# Programmer.net
KiCad netlist of a schematic drawn in Altium Designer
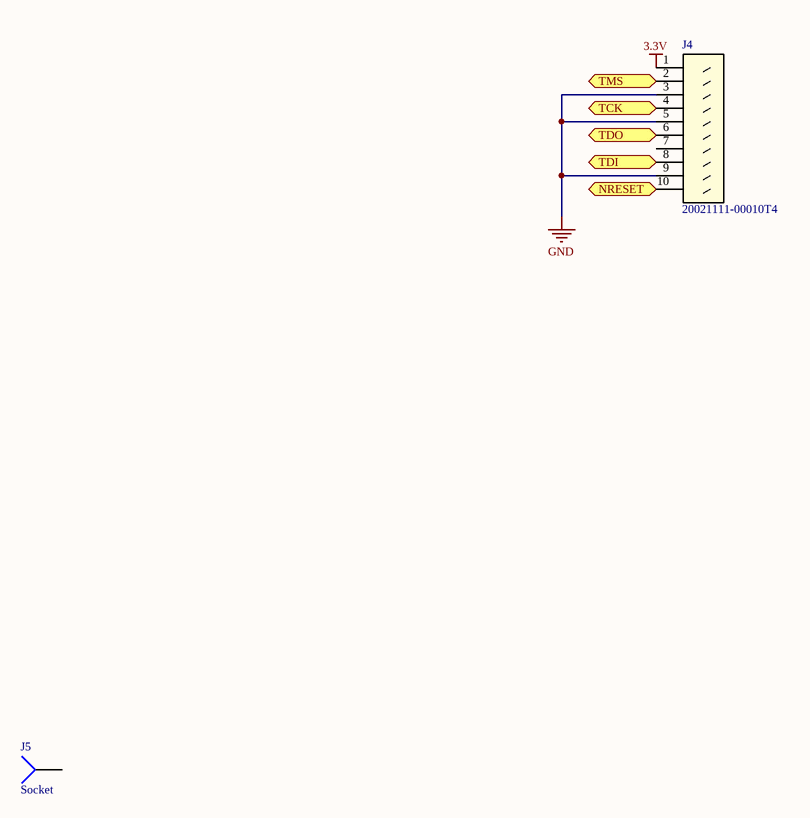
[diagram p0: Programmer.SchDoc]

(export (version "E")
  (design (tool "Eeschema 10.0.6"))
  (components
    (comp (ref "J4")
      (value "20021111-00010T4")
      (footprint "CONN_MINITEK_2X5")
      (description "Imported")
      (fields
        (field (name "MANUFACTURER_PART_NUMBER") "20021111-00010T4LF")
        (field (name "COPYRIGHT") "Copyright (C) 2015 Accelerated Designs. All rights reserved")
      )
      (libsource (lib "cortexjtag") (part "20021111-00010T4"))
    )
    (comp (ref "J5")
      (value "Socket")
      (footprint "PIN1")
      (fields (field (name "PUBLISHER") "Altium Limited"))
      (libsource (lib "Miscellaneous Connectors") (part "Socket"))
    )
  )
  (nets
    (net (code "1") (name "/NRESET") (class "Default")
      (node (ref "J4") (pin "10") (pinfunction "10_10") (pintype "passive"))
    )
    (net (code "2") (name "/TCK") (class "Default")
      (node (ref "J4") (pin "4") (pinfunction "4_4") (pintype "passive"))
    )
    (net (code "3") (name "/TDI") (class "Default")
      (node (ref "J4") (pin "8") (pinfunction "8_8") (pintype "passive"))
    )
    (net (code "4") (name "/TDO") (class "Default")
      (node (ref "J4") (pin "6") (pinfunction "6_6") (pintype "passive"))
    )
    (net (code "5") (name "/TMS") (class "Default")
      (node (ref "J4") (pin "2") (pinfunction "2_2") (pintype "passive"))
    )
    (net (code "6") (name "3.3V") (class "Default")
      (node (ref "J4") (pin "1") (pinfunction "1_1") (pintype "passive"))
    )
    (net (code "7") (name "GND") (class "Default")
      (node (ref "J4") (pin "3") (pinfunction "3_3") (pintype "passive"))
      (node (ref "J4") (pin "5") (pinfunction "5_5") (pintype "passive"))
      (node (ref "J4") (pin "9") (pinfunction "9_9") (pintype "passive"))
    )
    (net (code "8") (name "unconnected-(J4-Pad7)") (class "Default")
      (node (ref "J4") (pin "7") (pinfunction "7_7") (pintype "passive"))
    )
    (net (code "9") (name "unconnected-(J5-Pad1)") (class "Default")
      (node (ref "J5") (pin "1") (pinfunction "1_1") (pintype "passive"))
    )
  )
)
